# ServoMicro_plusPower.net
KiCad netlist of a schematic drawn in EAGLE
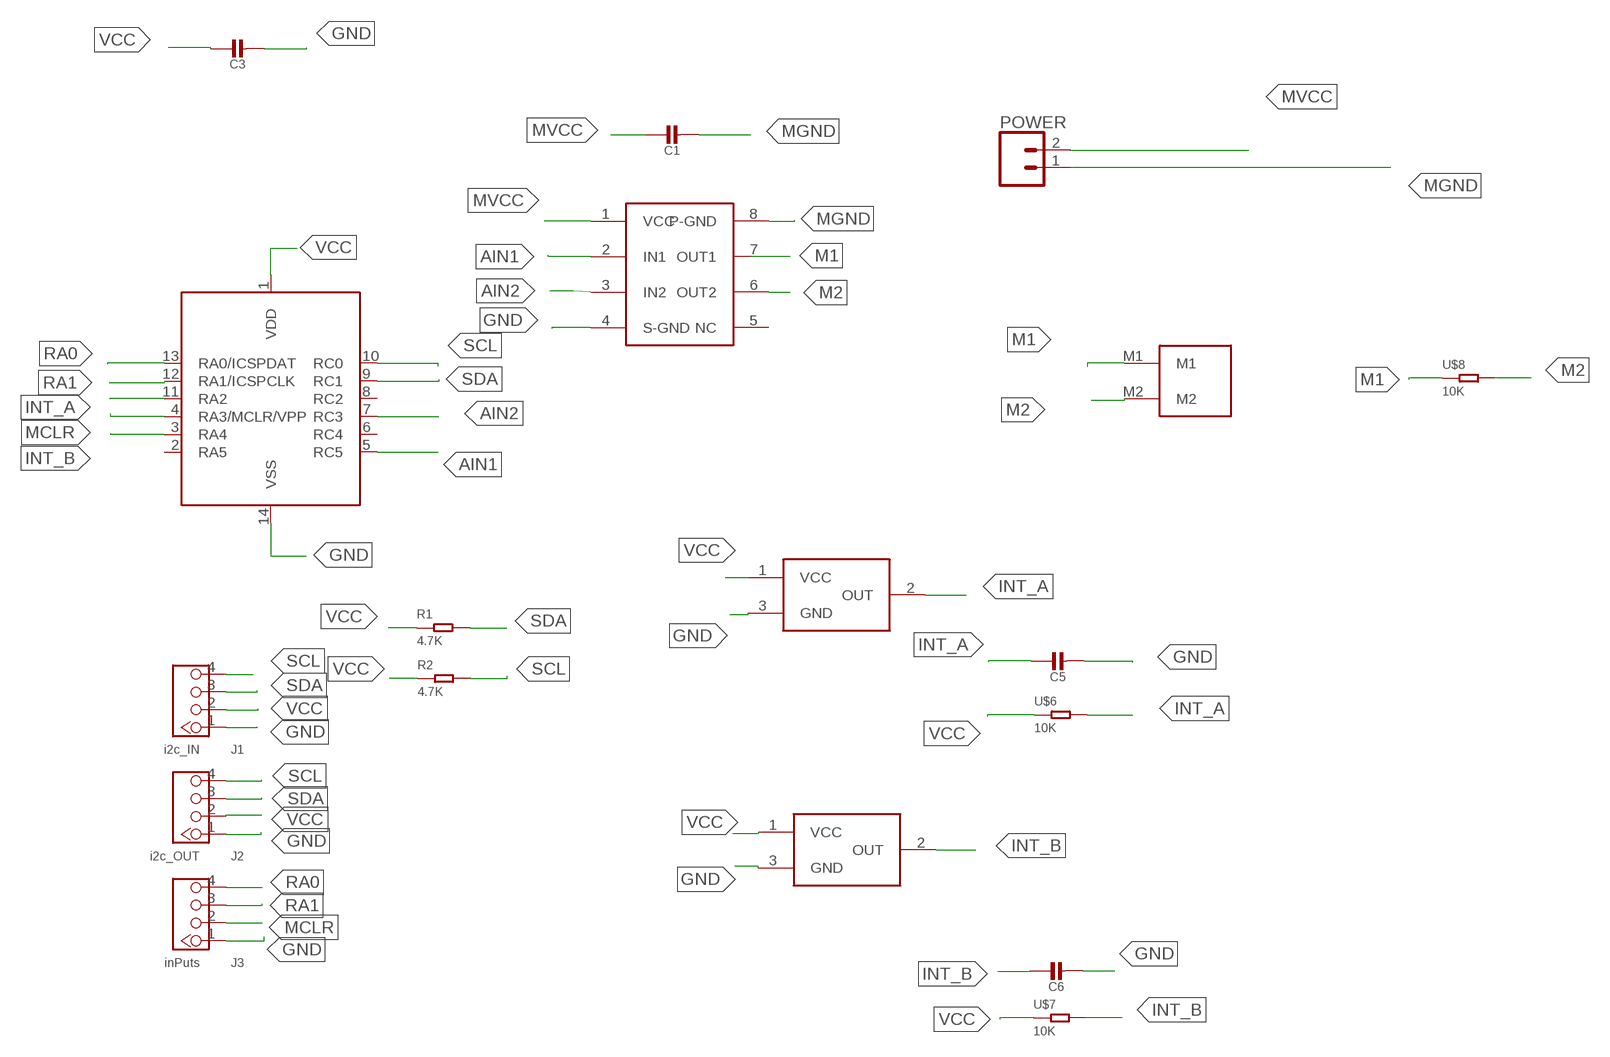
[diagram p0: schematic, sheet 1]

(export (version "E")
  (design (tool "Eeschema 10.0.6"))
  (components
    (comp (ref "C1")
      (value "CAP_CERAMIC0805-NOOUTLINE")
      (footprint "eagle-import:0805-NO")
      (libsource (lib "eagle-import") (part "CAP_CERAMIC0805-NOOUTLINE"))
    )
    (comp (ref "C3")
      (value "CAP_CERAMIC0805-NOOUTLINE")
      (footprint "eagle-import:0805-NO")
      (libsource (lib "eagle-import") (part "CAP_CERAMIC0805-NOOUTLINE"))
    )
    (comp (ref "C5")
      (value "CAP_CERAMIC0805-NOOUTLINE")
      (footprint "eagle-import:0805-NO")
      (libsource (lib "eagle-import") (part "CAP_CERAMIC0805-NOOUTLINE"))
    )
    (comp (ref "C6")
      (value "CAP_CERAMIC0805-NOOUTLINE")
      (footprint "eagle-import:0805-NO")
      (libsource (lib "eagle-import") (part "CAP_CERAMIC0805-NOOUTLINE"))
    )
    (comp (ref "J1")
      (value "i2c_IN")
      (footprint "eagle-import:HW4-2.0")
      (libsource (lib "eagle-import") (part "GROVE-CONNECTOR-DIP(4P-2.0)"))
    )
    (comp (ref "J2")
      (value "i2c_OUT")
      (footprint "eagle-import:HW4-2.0")
      (libsource (lib "eagle-import") (part "GROVE-CONNECTOR-DIP(4P-2.0)"))
    )
    (comp (ref "J3")
      (value "inPuts")
      (footprint "eagle-import:HW4-2.0")
      (libsource (lib "eagle-import") (part "GROVE-CONNECTOR-DIP(4P-2.0)"))
    )
    (comp (ref "POWER")
      (value "CONN_02-JST-2-PTH-NO_SILK")
      (footprint "eagle-import:JST-2-PTH-NS")
      (libsource (lib "eagle-import") (part "CONN_02-JST-2-PTH-NO_SILK"))
    )
    (comp (ref "R1")
      (value "4.7K")
      (footprint "eagle-import:R0805")
      (fields (field (name "MPN") "RC0805JR-074K7L"))
      (libsource (lib "eagle-import") (part "SMD-RES-4.7K-5%-1/8W(0805)"))
    )
    (comp (ref "R2")
      (value "4.7K")
      (footprint "eagle-import:R0805")
      (fields (field (name "MPN") "RC0805JR-074K7L"))
      (libsource (lib "eagle-import") (part "SMD-RES-4.7K-5%-1/8W(0805)"))
    )
    (comp (ref "U$1")
      (value "LB1938DFA_A")
      (footprint "eagle-import:MSOP8")
      (libsource (lib "eagle-import") (part "LB1938DFA_A"))
    )
    (comp (ref "U$2")
      (value "DRV5021-Q1")
      (footprint "eagle-import:SOT-23")
      (libsource (lib "eagle-import") (part "DRV5021-Q1"))
    )
    (comp (ref "U$3")
      (value "DRV5021-Q1")
      (footprint "eagle-import:SOT-23")
      (libsource (lib "eagle-import") (part "DRV5021-Q1"))
    )
    (comp (ref "U$4")
      (value "MICRO_MOTOR")
      (footprint "eagle-import:MICRO_MOTOR")
      (libsource (lib "eagle-import") (part "MICRO_MOTOR"))
    )
    (comp (ref "U$5")
      (value "PIC16F1503SOIC")
      (footprint "eagle-import:SO-14")
      (libsource (lib "eagle-import") (part "PIC16F1503SOIC"))
    )
    (comp (ref "U$6")
      (value "10K")
      (footprint "eagle-import:R0805")
      (fields (field (name "MPN") "RC0805FR-0710KL"))
      (libsource (lib "eagle-import") (part "SMD-RES-10K-1%-1/8W(0805)"))
    )
    (comp (ref "U$7")
      (value "10K")
      (footprint "eagle-import:R0805")
      (fields (field (name "MPN") "RC0805FR-0710KL"))
      (libsource (lib "eagle-import") (part "SMD-RES-10K-1%-1/8W(0805)"))
    )
    (comp (ref "U$8")
      (value "10K")
      (footprint "eagle-import:R0805")
      (fields (field (name "MPN") "RC0805FR-0710KL"))
      (libsource (lib "eagle-import") (part "SMD-RES-10K-1%-1/8W(0805)"))
    )
  )
  (nets
    (net (code "1") (name "AIN1") (class "Default")
      (node (ref "U$1") (pin "2") (pinfunction "IN1_2") (pintype "input"))
      (node (ref "U$5") (pin "5") (pinfunction "RC5_5") (pintype "bidirectional"))
    )
    (net (code "2") (name "AIN2") (class "Default")
      (node (ref "U$1") (pin "3") (pinfunction "IN2_3") (pintype "input"))
      (node (ref "U$5") (pin "7") (pinfunction "RC3_7") (pintype "bidirectional"))
    )
    (net (code "3") (name "GND") (class "Default")
      (node (ref "C3") (pin "2") (pinfunction "2_2") (pintype "passive"))
      (node (ref "C5") (pin "2") (pinfunction "2_2") (pintype "passive"))
      (node (ref "C6") (pin "2") (pinfunction "2_2") (pintype "passive"))
      (node (ref "J1") (pin "1") (pinfunction "1_1") (pintype "bidirectional"))
      (node (ref "J2") (pin "1") (pinfunction "1_1") (pintype "bidirectional"))
      (node (ref "J3") (pin "1") (pinfunction "1_1") (pintype "bidirectional"))
      (node (ref "U$1") (pin "4") (pinfunction "S-GND_4") (pintype "power_in"))
      (node (ref "U$2") (pin "3") (pinfunction "GND_3") (pintype "power_in"))
      (node (ref "U$3") (pin "3") (pinfunction "GND_3") (pintype "power_in"))
      (node (ref "U$5") (pin "14") (pinfunction "VSS_14") (pintype "power_in"))
    )
    (net (code "4") (name "INT_A") (class "Default")
      (node (ref "C5") (pin "1") (pinfunction "1_1") (pintype "passive"))
      (node (ref "U$2") (pin "2") (pinfunction "OUT_2") (pintype "output"))
      (node (ref "U$5") (pin "11") (pinfunction "RA2_11") (pintype "bidirectional"))
      (node (ref "U$6") (pin "2") (pinfunction "2_2") (pintype "passive"))
    )
    (net (code "5") (name "INT_B") (class "Default")
      (node (ref "C6") (pin "1") (pinfunction "1_1") (pintype "passive"))
      (node (ref "U$3") (pin "2") (pinfunction "OUT_2") (pintype "output"))
      (node (ref "U$5") (pin "3") (pinfunction "RA4_3") (pintype "bidirectional"))
      (node (ref "U$7") (pin "2") (pinfunction "2_2") (pintype "passive"))
    )
    (net (code "6") (name "M1") (class "Default")
      (node (ref "U$1") (pin "7") (pinfunction "OUT1_7") (pintype "output"))
      (node (ref "U$4") (pin "M1") (pinfunction "M1_M1") (pintype "input"))
      (node (ref "U$8") (pin "1") (pinfunction "1_1") (pintype "passive"))
    )
    (net (code "7") (name "M2") (class "Default")
      (node (ref "U$1") (pin "6") (pinfunction "OUT2_6") (pintype "output"))
      (node (ref "U$4") (pin "M2") (pinfunction "M2_M2") (pintype "input"))
      (node (ref "U$8") (pin "2") (pinfunction "2_2") (pintype "passive"))
    )
    (net (code "8") (name "MCLR") (class "Default")
      (node (ref "J3") (pin "2") (pinfunction "2_2") (pintype "bidirectional"))
      (node (ref "U$5") (pin "4") (pinfunction "RA3/MCLR/VPP_4") (pintype "input"))
    )
    (net (code "9") (name "MGND") (class "Default")
      (node (ref "C1") (pin "2") (pinfunction "2_2") (pintype "passive"))
      (node (ref "POWER") (pin "1") (pinfunction "1_1") (pintype "passive"))
      (node (ref "U$1") (pin "8") (pinfunction "P-GND_8") (pintype "power_in"))
    )
    (net (code "10") (name "MVCC") (class "Default")
      (node (ref "C1") (pin "1") (pinfunction "1_1") (pintype "passive"))
      (node (ref "POWER") (pin "2") (pinfunction "2_2") (pintype "passive"))
      (node (ref "U$1") (pin "1") (pinfunction "VCC_1") (pintype "power_in"))
    )
    (net (code "11") (name "RA0") (class "Default")
      (node (ref "J3") (pin "4") (pinfunction "4_4") (pintype "bidirectional"))
      (node (ref "U$5") (pin "13") (pinfunction "RA0/ICSPDAT_13") (pintype "bidirectional"))
    )
    (net (code "12") (name "RA1") (class "Default")
      (node (ref "J3") (pin "3") (pinfunction "3_3") (pintype "bidirectional"))
      (node (ref "U$5") (pin "12") (pinfunction "RA1/ICSPCLK_12") (pintype "bidirectional"))
    )
    (net (code "13") (name "SCL") (class "Default")
      (node (ref "J1") (pin "4") (pinfunction "4_4") (pintype "bidirectional"))
      (node (ref "J2") (pin "4") (pinfunction "4_4") (pintype "bidirectional"))
      (node (ref "R2") (pin "2") (pinfunction "2_2") (pintype "passive"))
      (node (ref "U$5") (pin "10") (pinfunction "RC0_10") (pintype "bidirectional"))
    )
    (net (code "14") (name "SDA") (class "Default")
      (node (ref "J1") (pin "3") (pinfunction "3_3") (pintype "bidirectional"))
      (node (ref "J2") (pin "3") (pinfunction "3_3") (pintype "bidirectional"))
      (node (ref "R1") (pin "2") (pinfunction "2_2") (pintype "passive"))
      (node (ref "U$5") (pin "9") (pinfunction "RC1_9") (pintype "bidirectional"))
    )
    (net (code "15") (name "VCC") (class "Default")
      (node (ref "C3") (pin "1") (pinfunction "1_1") (pintype "passive"))
      (node (ref "J1") (pin "2") (pinfunction "2_2") (pintype "bidirectional"))
      (node (ref "J2") (pin "2") (pinfunction "2_2") (pintype "bidirectional"))
      (node (ref "R1") (pin "1") (pinfunction "1_1") (pintype "passive"))
      (node (ref "R2") (pin "1") (pinfunction "1_1") (pintype "passive"))
      (node (ref "U$2") (pin "1") (pinfunction "VCC_1") (pintype "power_in"))
      (node (ref "U$3") (pin "1") (pinfunction "VCC_1") (pintype "power_in"))
      (node (ref "U$5") (pin "1") (pinfunction "VDD_1") (pintype "power_in"))
      (node (ref "U$6") (pin "1") (pinfunction "1_1") (pintype "passive"))
      (node (ref "U$7") (pin "1") (pinfunction "1_1") (pintype "passive"))
    )
    (net (code "16") (name "unconnected-(U$1-NC-Pad5)") (class "Default")
      (node (ref "U$1") (pin "5") (pinfunction "NC_5") (pintype "no_connect"))
    )
    (net (code "17") (name "unconnected-(U$5-RA5-Pad2)") (class "Default")
      (node (ref "U$5") (pin "2") (pinfunction "RA5_2") (pintype "bidirectional"))
    )
    (net (code "18") (name "unconnected-(U$5-RC2-Pad8)") (class "Default")
      (node (ref "U$5") (pin "8") (pinfunction "RC2_8") (pintype "bidirectional"))
    )
    (net (code "19") (name "unconnected-(U$5-RC4-Pad6)") (class "Default")
      (node (ref "U$5") (pin "6") (pinfunction "RC4_6") (pintype "bidirectional"))
    )
  )
)
